# 4_FPGA.net
KiCad netlist of a schematic drawn in Altium Designer
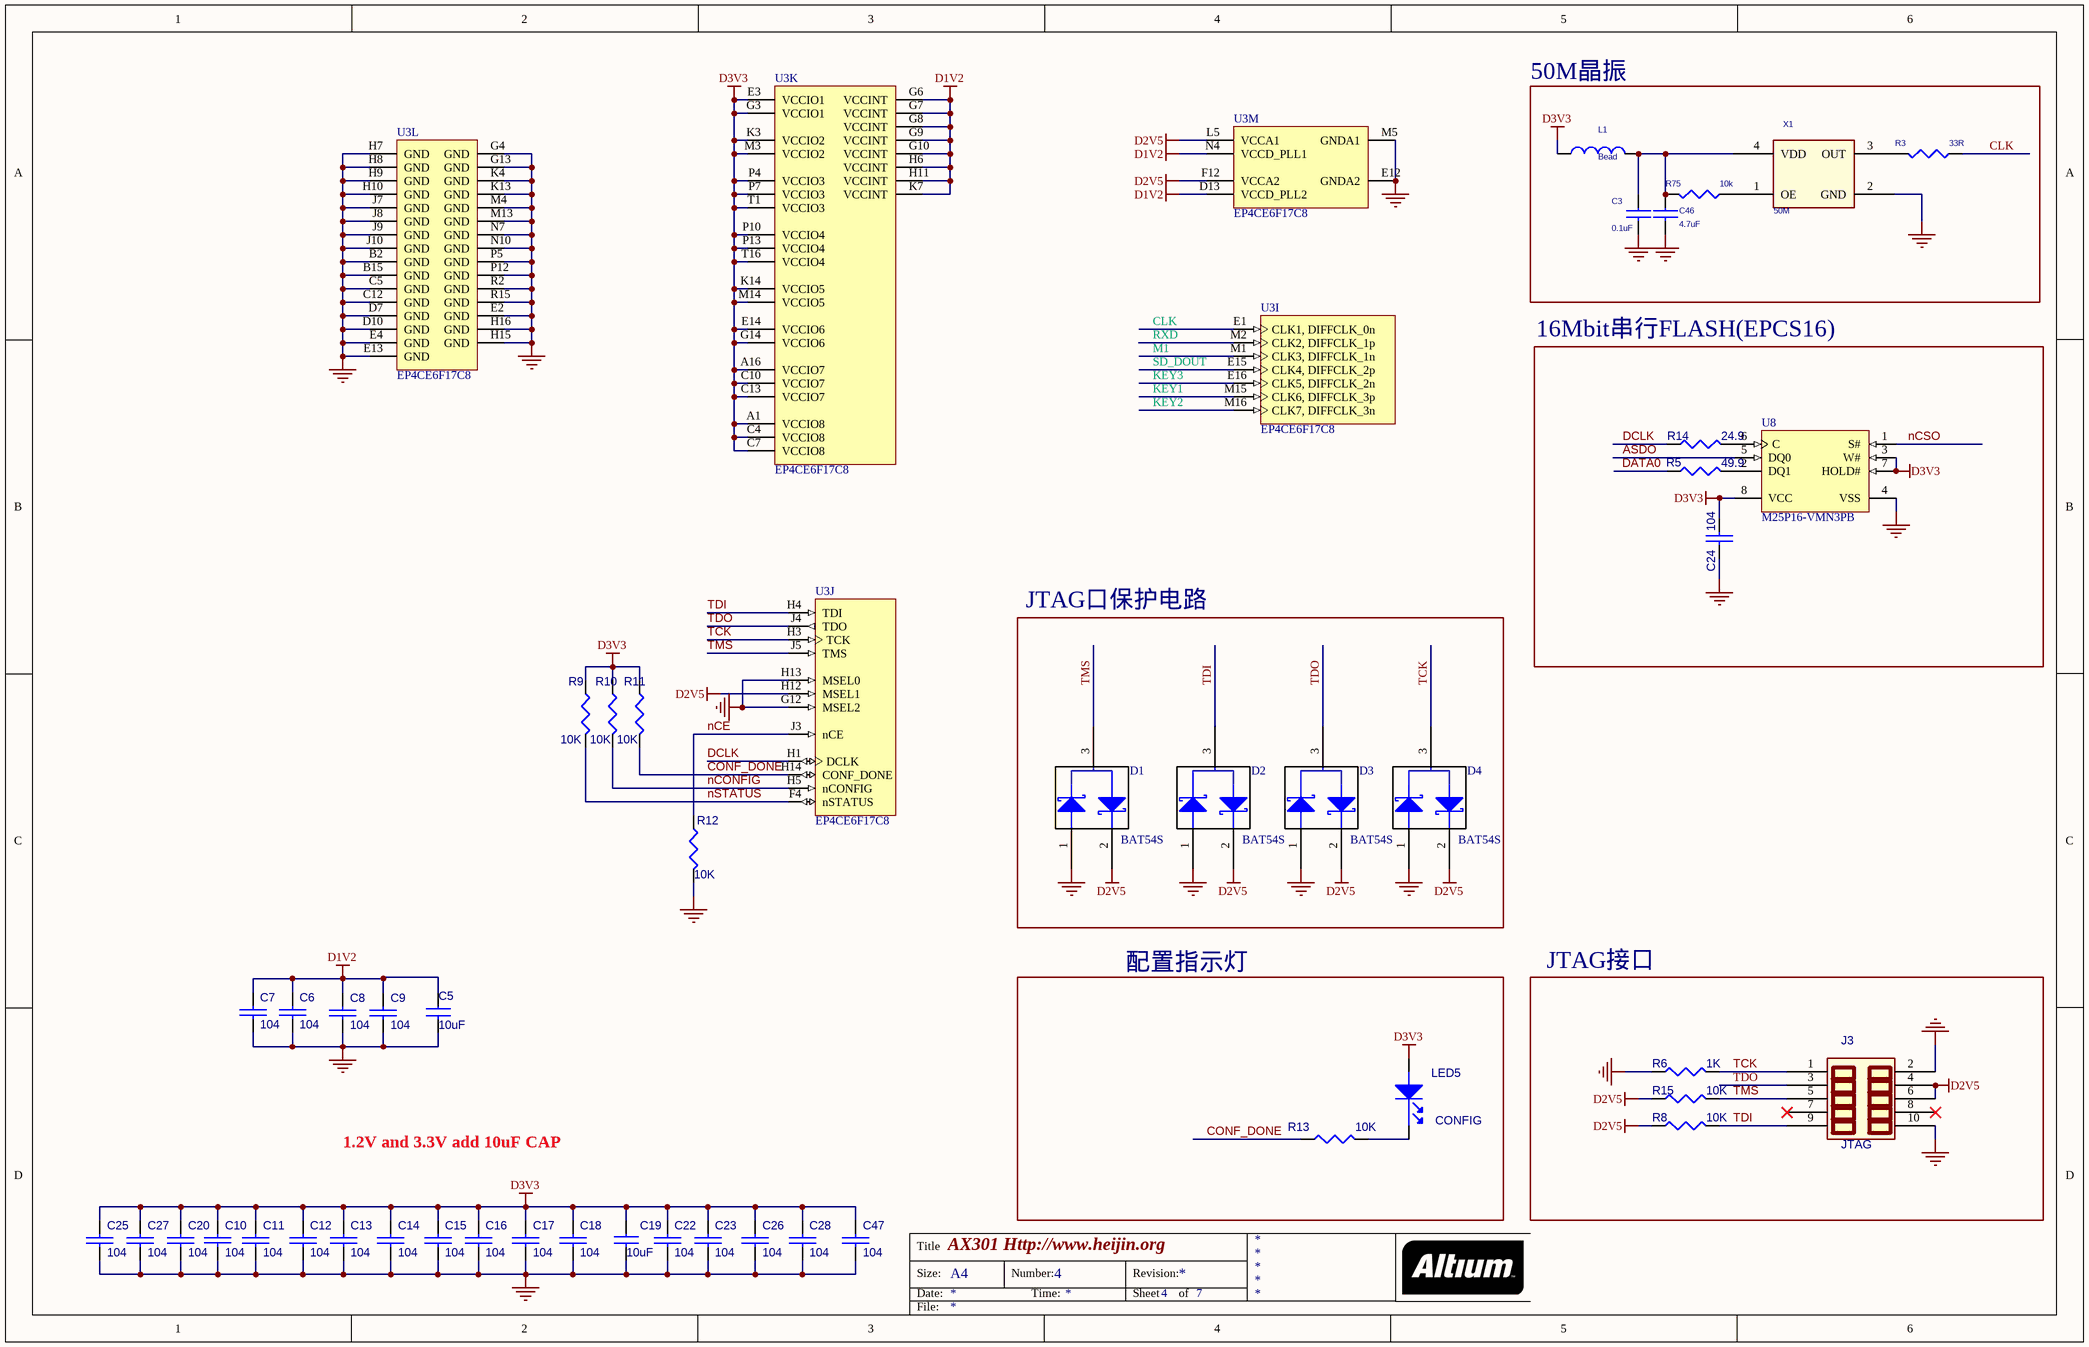
[diagram p0: 4_FPGA.SchDoc]

(export (version "E")
  (design (tool "Eeschema 10.0.6"))
  (components
    (comp (ref "C3") (value "0.1uF") (libsource (lib "*") (part "CAP NP_Dup2")))
    (comp (ref "C5") (value "10uF") (libsource (lib "*") (part "CAP NP_Dup2")))
    (comp (ref "C6") (value "104") (libsource (lib "*") (part "C_Dup4")))
    (comp (ref "C7") (value "104") (libsource (lib "*") (part "C_Dup4")))
    (comp (ref "C8") (value "104") (libsource (lib "*") (part "C_Dup4")))
    (comp (ref "C9") (value "104") (libsource (lib "*") (part "C_Dup4")))
    (comp (ref "C10") (value "104") (libsource (lib "*") (part "C_Dup4")))
    (comp (ref "C11") (value "104") (libsource (lib "*") (part "C_Dup4")))
    (comp (ref "C12") (value "104") (libsource (lib "*") (part "C_Dup4")))
    (comp (ref "C13") (value "104") (libsource (lib "*") (part "C_Dup4")))
    (comp (ref "C14") (value "104") (libsource (lib "*") (part "C_Dup4")))
    (comp (ref "C15") (value "104") (libsource (lib "*") (part "C_Dup4")))
    (comp (ref "C16") (value "104") (libsource (lib "*") (part "C_Dup4")))
    (comp (ref "C17") (value "104") (libsource (lib "*") (part "C_Dup4")))
    (comp (ref "C18") (value "104") (libsource (lib "*") (part "C_Dup4")))
    (comp (ref "C19") (value "10uF") (libsource (lib "*") (part "CAP NP_Dup2")))
    (comp (ref "C20") (value "104") (libsource (lib "*") (part "C_Dup4")))
    (comp (ref "C22") (value "104") (libsource (lib "*") (part "C_Dup4")))
    (comp (ref "C23") (value "104") (libsource (lib "*") (part "C_Dup4")))
    (comp (ref "C24") (value "104") (libsource (lib "*") (part "C_Dup4")))
    (comp (ref "C25") (value "104") (libsource (lib "*") (part "C_Dup4")))
    (comp (ref "C26") (value "104") (libsource (lib "*") (part "C_Dup4")))
    (comp (ref "C27") (value "104") (libsource (lib "*") (part "C_Dup4")))
    (comp (ref "C28") (value "104") (libsource (lib "*") (part "C_Dup4")))
    (comp (ref "C46") (value "4.7uF") (libsource (lib "*") (part "CAP NP_Dup2")))
    (comp (ref "C47") (value "104") (libsource (lib "*") (part "C_Dup4")))
    (comp (ref "D1")
      (value "BAT54S")
      (footprint "wfj_pcb:SOT23")
      (libsource (lib "ALINXSCH.REV.1.0") (part "BAV99"))
    )
    (comp (ref "D2")
      (value "BAT54S")
      (footprint "wfj_pcb:SOT23")
      (libsource (lib "ALINXSCH.REV.1.0") (part "BAV99"))
    )
    (comp (ref "D3")
      (value "BAT54S")
      (footprint "wfj_pcb:SOT23")
      (libsource (lib "ALINXSCH.REV.1.0") (part "BAV99"))
    )
    (comp (ref "D4")
      (value "BAT54S")
      (footprint "wfj_pcb:SOT23")
      (libsource (lib "ALINXSCH.REV.1.0") (part "BAV99"))
    )
    (comp (ref "J3") (value "JTAG") (footprint "JTAG-10") (libsource (lib "*") (part "JTAG-10_Dup1")))
    (comp (ref "L1") (value "Bead") (libsource (lib "*") (part "INDUCTOR")))
    (comp (ref "LED5") (value "CONFIG") (footprint "LEDSO") (libsource (lib "*") (part "LED_Dup1")))
    (comp (ref "R3") (value "33R") (libsource (lib "*") (part "RESISTOR")))
    (comp (ref "R5") (value "49.9") (footprint "0603") (libsource (lib "*") (part "R_Dup3")))
    (comp (ref "R6") (value "1K") (footprint "0603") (libsource (lib "*") (part "R_Dup2")))
    (comp (ref "R8") (value "10K") (footprint "0603") (libsource (lib "*") (part "R_Dup2")))
    (comp (ref "R9") (value "10K") (footprint "0603") (libsource (lib "*") (part "R_Dup3")))
    (comp (ref "R10") (value "10K") (footprint "0603") (libsource (lib "*") (part "R_Dup3")))
    (comp (ref "R11") (value "10K") (footprint "0603") (libsource (lib "*") (part "R_Dup3")))
    (comp (ref "R12") (value "10K") (footprint "0603") (libsource (lib "*") (part "R_Dup3")))
    (comp (ref "R13") (value "10K") (footprint "0603") (libsource (lib "*") (part "R_Dup1")))
    (comp (ref "R14") (value "24.9") (footprint "0603") (libsource (lib "*") (part "R_Dup3")))
    (comp (ref "R15") (value "10K") (footprint "0603") (libsource (lib "*") (part "R_Dup2")))
    (comp (ref "R75") (value "10k") (libsource (lib "*") (part "RESISTOR")))
    (comp (ref "U3")
      (value "EP4CE6F17C8")
      (footprint "Altera Cyclone IV E:FBGA256")
      (fields (field (name "PUBLISHER") "Altium Limited"))
      (libsource (lib "Altera Cyclone IV E") (part "EP4CE6F17C8"))
    )
    (comp (ref "U8")
      (value "M25P16-VMN3PB")
      (footprint "SO8")
      (description "16 Mb (x1) Automotive Serial NOR Flash Memory, 75 MHz, 2.7 to 3.6 V, 8-pin SO8 Narrow (MN), Tube")
      (fields (field (name "VOLTAGE") "2.7V-3.6V爘ISHIDDEN=T") (field (name "MANUFACTURER") "Micron"))
      (libsource (lib "Micron Memory Serial NOR Flash") (part "M25P16-VMN3PB"))
    )
    (comp (ref "X1") (value "50M") (libsource (lib "*") (part "OSC")))
  )
  (nets
    (net (code "1") (name "/ASDO") (class "Default")
      (node (ref "U8") (pin "5") (pinfunction "DQ0_5") (pintype "input"))
    )
    (net (code "2") (name "/CLK") (class "Default")
      (node (ref "R3") (pin "1") (pinfunction "1_1") (pintype "passive"))
      (node (ref "U3") (pin "E1") (pinfunction "CLK1,_DIFFCLK_0n_E1") (pintype "input"))
    )
    (net (code "3") (name "/CONF_DONE") (class "Default")
      (node (ref "R11") (pin "2") (pinfunction "2_2") (pintype "passive"))
      (node (ref "R13") (pin "1") (pinfunction "1_1") (pintype "passive"))
      (node (ref "U3") (pin "H14") (pinfunction "CONF_DONE_H14") (pintype "bidirectional"))
    )
    (net (code "4") (name "/DATA0") (class "Default")
      (node (ref "R5") (pin "1") (pinfunction "1_1") (pintype "passive"))
    )
    (net (code "5") (name "/DCLK") (class "Default")
      (node (ref "R14") (pin "1") (pinfunction "1_1") (pintype "passive"))
      (node (ref "U3") (pin "H1") (pinfunction "DCLK_H1") (pintype "bidirectional"))
    )
    (net (code "6") (name "/KEY1") (class "Default")
      (node (ref "U3") (pin "M15") (pinfunction "CLK6,_DIFFCLK_3p_M15") (pintype "input"))
    )
    (net (code "7") (name "/KEY2") (class "Default")
      (node (ref "U3") (pin "M16") (pinfunction "CLK7,_DIFFCLK_3n_M16") (pintype "input"))
    )
    (net (code "8") (name "/KEY3") (class "Default")
      (node (ref "U3") (pin "E16") (pinfunction "CLK5,_DIFFCLK_2n_E16") (pintype "input"))
    )
    (net (code "9") (name "/M1") (class "Default")
      (node (ref "U3") (pin "M1") (pinfunction "CLK3,_DIFFCLK_1n_M1") (pintype "input"))
    )
    (net (code "10") (name "/RXD") (class "Default")
      (node (ref "U3") (pin "M2") (pinfunction "CLK2,_DIFFCLK_1p_M2") (pintype "input"))
    )
    (net (code "11") (name "/SD_DOUT") (class "Default")
      (node (ref "U3") (pin "E15") (pinfunction "CLK4,_DIFFCLK_2p_E15") (pintype "input"))
    )
    (net (code "12") (name "/TCK") (class "Default")
      (node (ref "D4") (pin "3") (pinfunction "3_3") (pintype "passive"))
      (node (ref "J3") (pin "1") (pinfunction "1_1") (pintype "passive"))
      (node (ref "R6") (pin "2") (pinfunction "2_2") (pintype "passive"))
      (node (ref "U3") (pin "H3") (pinfunction "TCK_H3") (pintype "input"))
    )
    (net (code "13") (name "/TDI") (class "Default")
      (node (ref "D2") (pin "3") (pinfunction "3_3") (pintype "passive"))
      (node (ref "J3") (pin "9") (pinfunction "9_9") (pintype "passive"))
      (node (ref "R8") (pin "2") (pinfunction "2_2") (pintype "passive"))
      (node (ref "U3") (pin "H4") (pinfunction "TDI_H4") (pintype "input"))
    )
    (net (code "14") (name "/TDO") (class "Default")
      (node (ref "D3") (pin "3") (pinfunction "3_3") (pintype "passive"))
      (node (ref "J3") (pin "3") (pinfunction "3_3") (pintype "passive"))
      (node (ref "U3") (pin "J4") (pinfunction "TDO_J4") (pintype "output"))
    )
    (net (code "15") (name "/TMS") (class "Default")
      (node (ref "D1") (pin "3") (pinfunction "3_3") (pintype "passive"))
      (node (ref "J3") (pin "5") (pinfunction "5_5") (pintype "passive"))
      (node (ref "R15") (pin "2") (pinfunction "2_2") (pintype "passive"))
      (node (ref "U3") (pin "J5") (pinfunction "TMS_J5") (pintype "input"))
    )
    (net (code "16") (name "/nCE") (class "Default")
      (node (ref "R12") (pin "1") (pinfunction "1_1") (pintype "passive"))
      (node (ref "U3") (pin "J3") (pinfunction "nCE_J3") (pintype "input"))
    )
    (net (code "17") (name "/nCONFIG") (class "Default")
      (node (ref "R10") (pin "2") (pinfunction "2_2") (pintype "passive"))
      (node (ref "U3") (pin "H5") (pinfunction "nCONFIG_H5") (pintype "input"))
    )
    (net (code "18") (name "/nCSO") (class "Default")
      (node (ref "U8") (pin "1") (pinfunction "S#_1") (pintype "input"))
    )
    (net (code "19") (name "/nSTATUS") (class "Default")
      (node (ref "R9") (pin "2") (pinfunction "2_2") (pintype "passive"))
      (node (ref "U3") (pin "F4") (pinfunction "nSTATUS_F4") (pintype "bidirectional"))
    )
    (net (code "20") (name "D1V2") (class "Default")
      (node (ref "C5") (pin "1") (pinfunction "1_1") (pintype "passive"))
      (node (ref "C6") (pin "1") (pinfunction "1_1") (pintype "passive"))
      (node (ref "C7") (pin "1") (pinfunction "1_1") (pintype "passive"))
      (node (ref "C8") (pin "1") (pinfunction "1_1") (pintype "passive"))
      (node (ref "C9") (pin "1") (pinfunction "1_1") (pintype "passive"))
      (node (ref "U3") (pin "D13") (pinfunction "VCCD_PLL2_D13") (pintype "power_in"))
      (node (ref "U3") (pin "G10") (pinfunction "VCCINT_G10") (pintype "power_in"))
      (node (ref "U3") (pin "G6") (pinfunction "VCCINT_G6") (pintype "power_in"))
      (node (ref "U3") (pin "G7") (pinfunction "VCCINT_G7") (pintype "power_in"))
      (node (ref "U3") (pin "G8") (pinfunction "VCCINT_G8") (pintype "power_in"))
      (node (ref "U3") (pin "G9") (pinfunction "VCCINT_G9") (pintype "power_in"))
      (node (ref "U3") (pin "H11") (pinfunction "VCCINT_H11") (pintype "power_in"))
      (node (ref "U3") (pin "H6") (pinfunction "VCCINT_H6") (pintype "power_in"))
      (node (ref "U3") (pin "K7") (pinfunction "VCCINT_K7") (pintype "power_in"))
      (node (ref "U3") (pin "N4") (pinfunction "VCCD_PLL1_N4") (pintype "power_in"))
    )
    (net (code "21") (name "D2V5") (class "Default")
      (node (ref "D1") (pin "2") (pinfunction "2_2") (pintype "passive"))
      (node (ref "D2") (pin "2") (pinfunction "2_2") (pintype "passive"))
      (node (ref "D3") (pin "2") (pinfunction "2_2") (pintype "passive"))
      (node (ref "D4") (pin "2") (pinfunction "2_2") (pintype "passive"))
      (node (ref "J3") (pin "4") (pinfunction "4_4") (pintype "passive"))
      (node (ref "J3") (pin "6") (pinfunction "6_6") (pintype "passive"))
      (node (ref "R15") (pin "1") (pinfunction "1_1") (pintype "passive"))
      (node (ref "R8") (pin "1") (pinfunction "1_1") (pintype "passive"))
      (node (ref "U3") (pin "F12") (pinfunction "VCCA2_F12") (pintype "power_in"))
      (node (ref "U3") (pin "H12") (pinfunction "MSEL1_H12") (pintype "input"))
      (node (ref "U3") (pin "L5") (pinfunction "VCCA1_L5") (pintype "power_in"))
    )
    (net (code "22") (name "D3V3") (class "Default")
      (node (ref "C10") (pin "1") (pinfunction "1_1") (pintype "passive"))
      (node (ref "C11") (pin "1") (pinfunction "1_1") (pintype "passive"))
      (node (ref "C12") (pin "1") (pinfunction "1_1") (pintype "passive"))
      (node (ref "C13") (pin "1") (pinfunction "1_1") (pintype "passive"))
      (node (ref "C14") (pin "1") (pinfunction "1_1") (pintype "passive"))
      (node (ref "C15") (pin "1") (pinfunction "1_1") (pintype "passive"))
      (node (ref "C16") (pin "1") (pinfunction "1_1") (pintype "passive"))
      (node (ref "C17") (pin "1") (pinfunction "1_1") (pintype "passive"))
      (node (ref "C18") (pin "1") (pinfunction "1_1") (pintype "passive"))
      (node (ref "C19") (pin "1") (pinfunction "1_1") (pintype "passive"))
      (node (ref "C20") (pin "1") (pinfunction "1_1") (pintype "passive"))
      (node (ref "C22") (pin "1") (pinfunction "1_1") (pintype "passive"))
      (node (ref "C23") (pin "1") (pinfunction "1_1") (pintype "passive"))
      (node (ref "C24") (pin "2") (pinfunction "2_2") (pintype "passive"))
      (node (ref "C25") (pin "1") (pinfunction "1_1") (pintype "passive"))
      (node (ref "C26") (pin "1") (pinfunction "1_1") (pintype "passive"))
      (node (ref "C27") (pin "1") (pinfunction "1_1") (pintype "passive"))
      (node (ref "C28") (pin "1") (pinfunction "1_1") (pintype "passive"))
      (node (ref "C47") (pin "1") (pinfunction "1_1") (pintype "passive"))
      (node (ref "L1") (pin "1") (pinfunction "1_1") (pintype "passive"))
      (node (ref "LED5") (pin "1") (pinfunction "ANODE_1") (pintype "passive"))
      (node (ref "R10") (pin "1") (pinfunction "1_1") (pintype "passive"))
      (node (ref "R11") (pin "1") (pinfunction "1_1") (pintype "passive"))
      (node (ref "R9") (pin "1") (pinfunction "1_1") (pintype "passive"))
      (node (ref "U3") (pin "A1") (pinfunction "VCCIO8_A1") (pintype "power_in"))
      (node (ref "U3") (pin "A16") (pinfunction "VCCIO7_A16") (pintype "power_in"))
      (node (ref "U3") (pin "C10") (pinfunction "VCCIO7_C10") (pintype "power_in"))
      (node (ref "U3") (pin "C13") (pinfunction "VCCIO7_C13") (pintype "power_in"))
      (node (ref "U3") (pin "C4") (pinfunction "VCCIO8_C4") (pintype "power_in"))
      (node (ref "U3") (pin "C7") (pinfunction "VCCIO8_C7") (pintype "power_in"))
      (node (ref "U3") (pin "E14") (pinfunction "VCCIO6_E14") (pintype "power_in"))
      (node (ref "U3") (pin "E3") (pinfunction "VCCIO1_E3") (pintype "power_in"))
      (node (ref "U3") (pin "G14") (pinfunction "VCCIO6_G14") (pintype "power_in"))
      (node (ref "U3") (pin "G3") (pinfunction "VCCIO1_G3") (pintype "power_in"))
      (node (ref "U3") (pin "K14") (pinfunction "VCCIO5_K14") (pintype "power_in"))
      (node (ref "U3") (pin "K3") (pinfunction "VCCIO2_K3") (pintype "power_in"))
      (node (ref "U3") (pin "M14") (pinfunction "VCCIO5_M14") (pintype "power_in"))
      (node (ref "U3") (pin "M3") (pinfunction "VCCIO2_M3") (pintype "power_in"))
      (node (ref "U3") (pin "P10") (pinfunction "VCCIO4_P10") (pintype "power_in"))
      (node (ref "U3") (pin "P13") (pinfunction "VCCIO4_P13") (pintype "power_in"))
      (node (ref "U3") (pin "P4") (pinfunction "VCCIO3_P4") (pintype "power_in"))
      (node (ref "U3") (pin "P7") (pinfunction "VCCIO3_P7") (pintype "power_in"))
      (node (ref "U3") (pin "T1") (pinfunction "VCCIO3_T1") (pintype "power_in"))
      (node (ref "U3") (pin "T16") (pinfunction "VCCIO4_T16") (pintype "power_in"))
      (node (ref "U8") (pin "3") (pinfunction "W#_3") (pintype "input"))
      (node (ref "U8") (pin "7") (pinfunction "HOLD#_7") (pintype "input"))
      (node (ref "U8") (pin "8") (pinfunction "VCC_8") (pintype "power_in"))
    )
    (net (code "23") (name "GND") (class "Default")
      (node (ref "C10") (pin "2") (pinfunction "2_2") (pintype "passive"))
      (node (ref "C11") (pin "2") (pinfunction "2_2") (pintype "passive"))
      (node (ref "C12") (pin "2") (pinfunction "2_2") (pintype "passive"))
      (node (ref "C13") (pin "2") (pinfunction "2_2") (pintype "passive"))
      (node (ref "C14") (pin "2") (pinfunction "2_2") (pintype "passive"))
      (node (ref "C15") (pin "2") (pinfunction "2_2") (pintype "passive"))
      (node (ref "C16") (pin "2") (pinfunction "2_2") (pintype "passive"))
      (node (ref "C17") (pin "2") (pinfunction "2_2") (pintype "passive"))
      (node (ref "C18") (pin "2") (pinfunction "2_2") (pintype "passive"))
      (node (ref "C19") (pin "2") (pinfunction "2_2") (pintype "passive"))
      (node (ref "C20") (pin "2") (pinfunction "2_2") (pintype "passive"))
      (node (ref "C22") (pin "2") (pinfunction "2_2") (pintype "passive"))
      (node (ref "C23") (pin "2") (pinfunction "2_2") (pintype "passive"))
      (node (ref "C24") (pin "1") (pinfunction "1_1") (pintype "passive"))
      (node (ref "C25") (pin "2") (pinfunction "2_2") (pintype "passive"))
      (node (ref "C26") (pin "2") (pinfunction "2_2") (pintype "passive"))
      (node (ref "C27") (pin "2") (pinfunction "2_2") (pintype "passive"))
      (node (ref "C28") (pin "2") (pinfunction "2_2") (pintype "passive"))
      (node (ref "C3") (pin "2") (pinfunction "2_2") (pintype "passive"))
      (node (ref "C46") (pin "2") (pinfunction "2_2") (pintype "passive"))
      (node (ref "C47") (pin "2") (pinfunction "2_2") (pintype "passive"))
      (node (ref "C5") (pin "2") (pinfunction "2_2") (pintype "passive"))
      (node (ref "C6") (pin "2") (pinfunction "2_2") (pintype "passive"))
      (node (ref "C7") (pin "2") (pinfunction "2_2") (pintype "passive"))
      (node (ref "C8") (pin "2") (pinfunction "2_2") (pintype "passive"))
      (node (ref "C9") (pin "2") (pinfunction "2_2") (pintype "passive"))
      (node (ref "D1") (pin "1") (pinfunction "1_1") (pintype "passive"))
      (node (ref "D2") (pin "1") (pinfunction "1_1") (pintype "passive"))
      (node (ref "D3") (pin "1") (pinfunction "1_1") (pintype "passive"))
      (node (ref "D4") (pin "1") (pinfunction "1_1") (pintype "passive"))
      (node (ref "J3") (pin "10") (pinfunction "10_10") (pintype "passive"))
      (node (ref "J3") (pin "2") (pinfunction "2_2") (pintype "passive"))
      (node (ref "R12") (pin "2") (pinfunction "2_2") (pintype "passive"))
      (node (ref "R6") (pin "1") (pinfunction "1_1") (pintype "passive"))
      (node (ref "U3") (pin "B15") (pinfunction "GND_B15") (pintype "power_in"))
      (node (ref "U3") (pin "B2") (pinfunction "GND_B2") (pintype "power_in"))
      (node (ref "U3") (pin "C12") (pinfunction "GND_C12") (pintype "power_in"))
      (node (ref "U3") (pin "C5") (pinfunction "GND_C5") (pintype "power_in"))
      (node (ref "U3") (pin "D10") (pinfunction "GND_D10") (pintype "power_in"))
      (node (ref "U3") (pin "D7") (pinfunction "GND_D7") (pintype "power_in"))
      (node (ref "U3") (pin "E12") (pinfunction "GNDA2_E12") (pintype "power_in"))
      (node (ref "U3") (pin "E13") (pinfunction "GND_E13") (pintype "power_in"))
      (node (ref "U3") (pin "E2") (pinfunction "GND_E2") (pintype "power_in"))
      (node (ref "U3") (pin "E4") (pinfunction "GND_E4") (pintype "power_in"))
      (node (ref "U3") (pin "G12") (pinfunction "MSEL2_G12") (pintype "input"))
      (node (ref "U3") (pin "G13") (pinfunction "GND_G13") (pintype "power_in"))
      (node (ref "U3") (pin "G4") (pinfunction "GND_G4") (pintype "power_in"))
      (node (ref "U3") (pin "H10") (pinfunction "GND_H10") (pintype "power_in"))
      (node (ref "U3") (pin "H13") (pinfunction "MSEL0_H13") (pintype "input"))
      (node (ref "U3") (pin "H15") (pinfunction "GND_H15") (pintype "power_in"))
      (node (ref "U3") (pin "H16") (pinfunction "GND_H16") (pintype "power_in"))
      (node (ref "U3") (pin "H7") (pinfunction "GND_H7") (pintype "power_in"))
      (node (ref "U3") (pin "H8") (pinfunction "GND_H8") (pintype "power_in"))
      (node (ref "U3") (pin "H9") (pinfunction "GND_H9") (pintype "power_in"))
      (node (ref "U3") (pin "J10") (pinfunction "GND_J10") (pintype "power_in"))
      (node (ref "U3") (pin "J7") (pinfunction "GND_J7") (pintype "power_in"))
      (node (ref "U3") (pin "J8") (pinfunction "GND_J8") (pintype "power_in"))
      (node (ref "U3") (pin "J9") (pinfunction "GND_J9") (pintype "power_in"))
      (node (ref "U3") (pin "K13") (pinfunction "GND_K13") (pintype "power_in"))
      (node (ref "U3") (pin "K4") (pinfunction "GND_K4") (pintype "power_in"))
      (node (ref "U3") (pin "M13") (pinfunction "GND_M13") (pintype "power_in"))
      (node (ref "U3") (pin "M4") (pinfunction "GND_M4") (pintype "power_in"))
      (node (ref "U3") (pin "M5") (pinfunction "GNDA1_M5") (pintype "power_in"))
      (node (ref "U3") (pin "N10") (pinfunction "GND_N10") (pintype "power_in"))
      (node (ref "U3") (pin "N7") (pinfunction "GND_N7") (pintype "power_in"))
      (node (ref "U3") (pin "P12") (pinfunction "GND_P12") (pintype "power_in"))
      (node (ref "U3") (pin "P5") (pinfunction "GND_P5") (pintype "power_in"))
      (node (ref "U3") (pin "R15") (pinfunction "GND_R15") (pintype "power_in"))
      (node (ref "U3") (pin "R2") (pinfunction "GND_R2") (pintype "power_in"))
      (node (ref "U8") (pin "4") (pinfunction "VSS_4") (pintype "power_in"))
      (node (ref "X1") (pin "2") (pinfunction "GND_2") (pintype "passive"))
    )
    (net (code "24") (name "Net-(LED5-CATHODE)") (class "Default")
      (node (ref "LED5") (pin "2") (pinfunction "CATHODE_2") (pintype "passive"))
      (node (ref "R13") (pin "2") (pinfunction "2_2") (pintype "passive"))
    )
    (net (code "25") (name "Net-(U8-C)") (class "Default")
      (node (ref "R14") (pin "2") (pinfunction "2_2") (pintype "passive"))
      (node (ref "U8") (pin "6") (pinfunction "C_6") (pintype "input"))
    )
    (net (code "26") (name "Net-(U8-DQ1)") (class "Default")
      (node (ref "R5") (pin "2") (pinfunction "2_2") (pintype "passive"))
      (node (ref "U8") (pin "2") (pinfunction "DQ1_2") (pintype "tri_state"))
    )
    (net (code "27") (name "Net-(X1-OE)") (class "Default")
      (node (ref "R75") (pin "1") (pinfunction "1_1") (pintype "passive"))
      (node (ref "X1") (pin "1") (pinfunction "OE_1") (pintype "passive"))
    )
    (net (code "28") (name "Net-(X1-OUT)") (class "Default")
      (node (ref "R3") (pin "2") (pinfunction "2_2") (pintype "passive"))
      (node (ref "X1") (pin "3") (pinfunction "OUT_3") (pintype "passive"))
    )
    (net (code "29") (name "Net-(X1-VDD)") (class "Default")
      (node (ref "C3") (pin "1") (pinfunction "1_1") (pintype "passive"))
      (node (ref "C46") (pin "1") (pinfunction "1_1") (pintype "passive"))
      (node (ref "L1") (pin "2") (pinfunction "2_2") (pintype "passive"))
      (node (ref "R75") (pin "2") (pinfunction "2_2") (pintype "passive"))
      (node (ref "X1") (pin "4") (pinfunction "VDD_4") (pintype "passive"))
    )
    (net (code "30") (name "unconnected-(J3-Pad7)") (class "Default")
      (node (ref "J3") (pin "7") (pinfunction "7_7") (pintype "passive+no_connect"))
    )
    (net (code "31") (name "unconnected-(J3-Pad8)") (class "Default")
      (node (ref "J3") (pin "8") (pinfunction "8_8") (pintype "passive+no_connect"))
    )
  )
)
